# RS232.net
KiCad netlist of a schematic drawn in Altium Designer
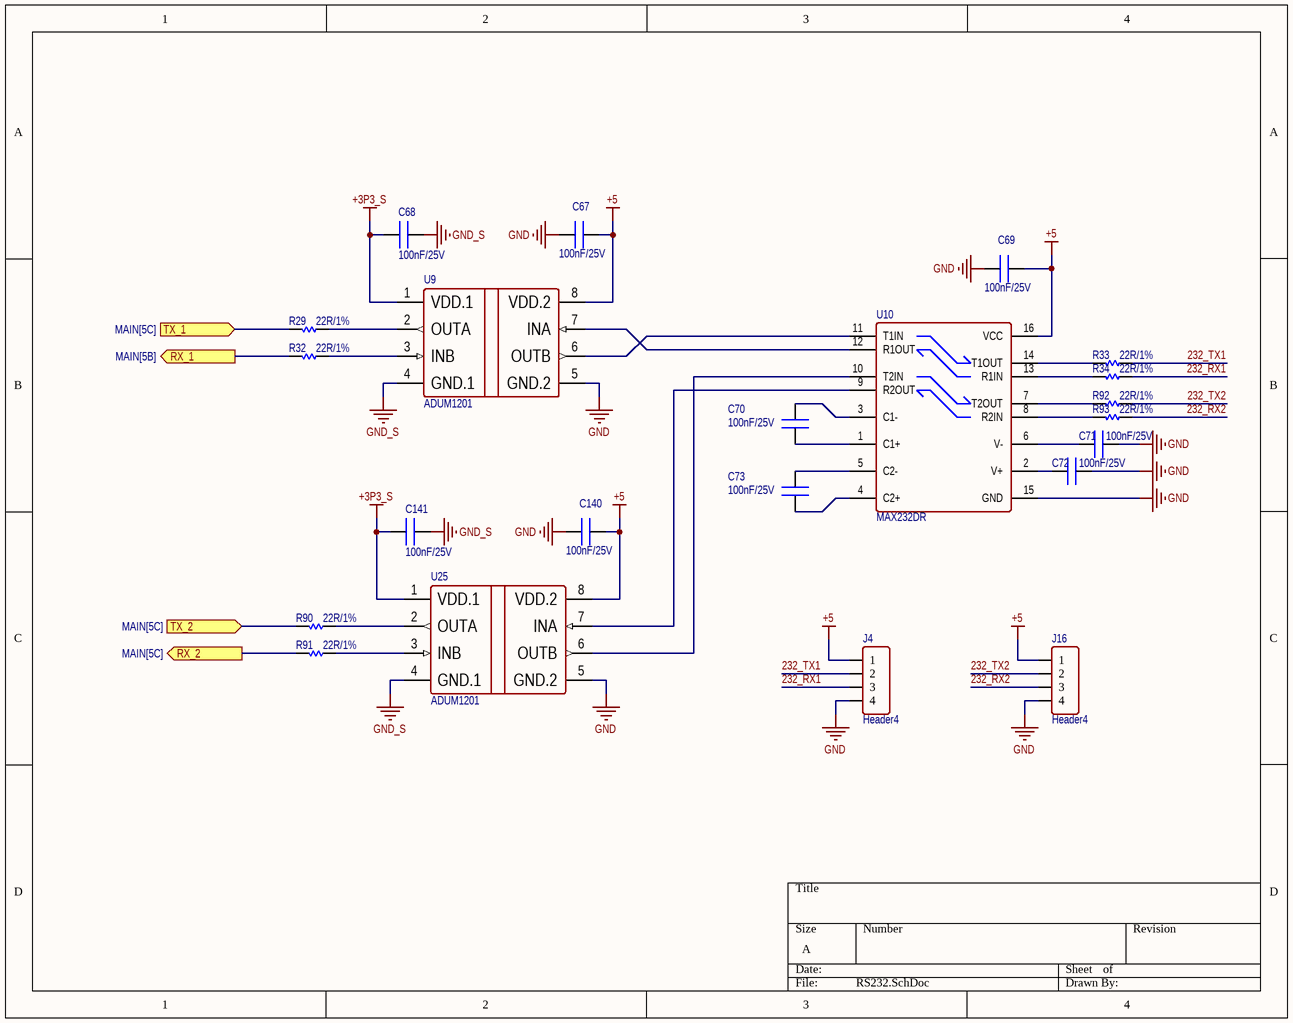
[diagram p0: RS232.SchDoc]

(export (version "E")
  (design (tool "Eeschema 10.0.6"))
  (components
    (comp (ref "C67")
      (value "100nF/25V")
      (footprint "CN-SMD-0603")
      (description "CL10B104KA8NNNC")
      (libsource (lib "Library") (part "CN"))
    )
    (comp (ref "C68")
      (value "100nF/25V")
      (footprint "CN-SMD-0603")
      (description "CL10B104KA8NNNC")
      (libsource (lib "Library") (part "CN"))
    )
    (comp (ref "C69")
      (value "100nF/25V")
      (footprint "CN-SMD-0603")
      (description "CL10B104KA8NNNC")
      (libsource (lib "Library") (part "CN"))
    )
    (comp (ref "C70")
      (value "100nF/25V")
      (footprint "CN-SMD-0603")
      (description "CL10B104KA8NNNC")
      (libsource (lib "Library") (part "CN"))
    )
    (comp (ref "C71")
      (value "100nF/25V")
      (footprint "CN-SMD-0603")
      (description "CL10B104KA8NNNC")
      (libsource (lib "Library") (part "CN"))
    )
    (comp (ref "C72")
      (value "100nF/25V")
      (footprint "CN-SMD-0603")
      (description "CL10B104KA8NNNC")
      (libsource (lib "Library") (part "CN"))
    )
    (comp (ref "C73")
      (value "100nF/25V")
      (footprint "CN-SMD-0603")
      (description "CL10B104KA8NNNC")
      (libsource (lib "Library") (part "CN"))
    )
    (comp (ref "C140")
      (value "100nF/25V")
      (footprint "CN-SMD-0603")
      (description "CL10B104KA8NNNC")
      (libsource (lib "Library") (part "CN"))
    )
    (comp (ref "C141")
      (value "100nF/25V")
      (footprint "CN-SMD-0603")
      (description "CL10B104KA8NNNC")
      (libsource (lib "Library") (part "CN"))
    )
    (comp (ref "J4")
      (value "Header4")
      (footprint "XH2.54-4-DIP")
      (description "Connector 4")
      (fields
        (field (name "MANUFACTURER") "Würth Elektronik eiSos GmbH")
        (field (name "PARTNO") "613002143121")
        (field (name "CREATED BY") "Karrer Zheng")
      )
      (libsource (lib "Library") (part "Header4"))
    )
    (comp (ref "J16")
      (value "Header4")
      (footprint "XH2.54-4-DIP")
      (description "Connector 4")
      (fields
        (field (name "MANUFACTURER") "Würth Elektronik eiSos GmbH")
        (field (name "PARTNO") "613002143121")
        (field (name "CREATED BY") "Karrer Zheng")
      )
      (libsource (lib "Library") (part "Header4"))
    )
    (comp (ref "R29")
      (value "22R/1%")
      (footprint "RES-SMD-0603")
      (description "ERJ-3EKF22R0V")
      (libsource (lib "Library") (part "Res-SMD"))
    )
    (comp (ref "R32")
      (value "22R/1%")
      (footprint "RES-SMD-0603")
      (description "ERJ-3EKF22R0V")
      (libsource (lib "Library") (part "Res-SMD"))
    )
    (comp (ref "R33")
      (value "22R/1%")
      (footprint "RES-SMD-0603")
      (description "ERJ-3EKF22R0V")
      (libsource (lib "Library") (part "Res-SMD"))
    )
    (comp (ref "R34")
      (value "22R/1%")
      (footprint "RES-SMD-0603")
      (description "ERJ-3EKF22R0V")
      (libsource (lib "Library") (part "Res-SMD"))
    )
    (comp (ref "R90")
      (value "22R/1%")
      (footprint "RES-SMD-0603")
      (description "ERJ-3EKF22R0V")
      (libsource (lib "Library") (part "Res-SMD"))
    )
    (comp (ref "R91")
      (value "22R/1%")
      (footprint "RES-SMD-0603")
      (description "ERJ-3EKF22R0V")
      (libsource (lib "Library") (part "Res-SMD"))
    )
    (comp (ref "R92")
      (value "22R/1%")
      (footprint "RES-SMD-0603")
      (description "ERJ-3EKF22R0V")
      (libsource (lib "Library") (part "Res-SMD"))
    )
    (comp (ref "R93")
      (value "22R/1%")
      (footprint "RES-SMD-0603")
      (description "ERJ-3EKF22R0V")
      (libsource (lib "Library") (part "Res-SMD"))
    )
    (comp (ref "U9")
      (value "ADUM1201")
      (footprint "SO8")
      (description "Dual-Channel Digital Isolators")
      (libsource (lib "Library") (part "ADUM1201"))
    )
    (comp (ref "U10") (value "MAX232DR") (footprint "SO16") (libsource (lib "Library") (part "MAX3232")))
    (comp (ref "U25")
      (value "ADUM1201")
      (footprint "SO8")
      (description "Dual-Channel Digital Isolators")
      (libsource (lib "Library") (part "ADUM1201"))
    )
  )
  (nets
    (net (code "1") (name "+3P3_S") (class "Default")
      (node (ref "C141") (pin "2") (pinfunction "2_2") (pintype "passive"))
      (node (ref "C68") (pin "2") (pinfunction "2_2") (pintype "passive"))
      (node (ref "U25") (pin "1") (pinfunction "VDD.1_1") (pintype "passive"))
      (node (ref "U9") (pin "1") (pinfunction "VDD.1_1") (pintype "passive"))
    )
    (net (code "2") (name "+5") (class "Default")
      (node (ref "C140") (pin "1") (pinfunction "1_1") (pintype "passive"))
      (node (ref "C67") (pin "1") (pinfunction "1_1") (pintype "passive"))
      (node (ref "C69") (pin "1") (pinfunction "1_1") (pintype "passive"))
      (node (ref "J16") (pin "1") (pinfunction "1_1") (pintype "passive"))
      (node (ref "J4") (pin "1") (pinfunction "1_1") (pintype "passive"))
      (node (ref "U10") (pin "16") (pinfunction "VCC_16") (pintype "power_in"))
      (node (ref "U25") (pin "8") (pinfunction "VDD.2_8") (pintype "passive"))
      (node (ref "U9") (pin "8") (pinfunction "VDD.2_8") (pintype "passive"))
    )
    (net (code "3") (name "/232_RX1") (class "Default")
      (node (ref "J4") (pin "3") (pinfunction "3_3") (pintype "passive"))
      (node (ref "R34") (pin "1") (pinfunction "1_1") (pintype "passive"))
    )
    (net (code "4") (name "/232_RX2") (class "Default")
      (node (ref "J16") (pin "3") (pinfunction "3_3") (pintype "passive"))
      (node (ref "R93") (pin "1") (pinfunction "1_1") (pintype "passive"))
    )
    (net (code "5") (name "/232_TX1") (class "Default")
      (node (ref "J4") (pin "2") (pinfunction "2_2") (pintype "passive"))
      (node (ref "R33") (pin "1") (pinfunction "1_1") (pintype "passive"))
    )
    (net (code "6") (name "/232_TX2") (class "Default")
      (node (ref "J16") (pin "2") (pinfunction "2_2") (pintype "passive"))
      (node (ref "R92") (pin "1") (pinfunction "1_1") (pintype "passive"))
    )
    (net (code "7") (name "/RX_1") (class "Default")
      (node (ref "R32") (pin "2") (pinfunction "2_2") (pintype "passive"))
    )
    (net (code "8") (name "/RX_2") (class "Default")
      (node (ref "R91") (pin "2") (pinfunction "2_2") (pintype "passive"))
    )
    (net (code "9") (name "/TX_1") (class "Default")
      (node (ref "R29") (pin "2") (pinfunction "2_2") (pintype "passive"))
    )
    (net (code "10") (name "/TX_2") (class "Default")
      (node (ref "R90") (pin "2") (pinfunction "2_2") (pintype "passive"))
    )
    (net (code "11") (name "GND") (class "Default")
      (node (ref "C140") (pin "2") (pinfunction "2_2") (pintype "passive"))
      (node (ref "C67") (pin "2") (pinfunction "2_2") (pintype "passive"))
      (node (ref "C69") (pin "2") (pinfunction "2_2") (pintype "passive"))
      (node (ref "C71") (pin "1") (pinfunction "1_1") (pintype "passive"))
      (node (ref "C72") (pin "1") (pinfunction "1_1") (pintype "passive"))
      (node (ref "J16") (pin "4") (pinfunction "4_4") (pintype "passive"))
      (node (ref "J4") (pin "4") (pinfunction "4_4") (pintype "passive"))
      (node (ref "U10") (pin "15") (pinfunction "GND_15") (pintype "power_in"))
      (node (ref "U25") (pin "5") (pinfunction "GND.2_5") (pintype "passive"))
      (node (ref "U9") (pin "5") (pinfunction "GND.2_5") (pintype "passive"))
    )
    (net (code "12") (name "GND_S") (class "Default")
      (node (ref "C141") (pin "1") (pinfunction "1_1") (pintype "passive"))
      (node (ref "C68") (pin "1") (pinfunction "1_1") (pintype "passive"))
      (node (ref "U25") (pin "4") (pinfunction "GND.1_4") (pintype "passive"))
      (node (ref "U9") (pin "4") (pinfunction "GND.1_4") (pintype "passive"))
    )
    (net (code "13") (name "Net-(U9-INB)") (class "Default")
      (node (ref "R32") (pin "1") (pinfunction "1_1") (pintype "passive"))
      (node (ref "U9") (pin "3") (pinfunction "INB_3") (pintype "input"))
    )
    (net (code "14") (name "Net-(U9-OUTA)") (class "Default")
      (node (ref "R29") (pin "1") (pinfunction "1_1") (pintype "passive"))
      (node (ref "U9") (pin "2") (pinfunction "OUTA_2") (pintype "output"))
    )
    (net (code "15") (name "Net-(U10-C1+)") (class "Default")
      (node (ref "C70") (pin "1") (pinfunction "1_1") (pintype "passive"))
      (node (ref "U10") (pin "1") (pinfunction "C1+_1") (pintype "power_in"))
    )
    (net (code "16") (name "Net-(U10-C1-)") (class "Default")
      (node (ref "C70") (pin "2") (pinfunction "2_2") (pintype "passive"))
      (node (ref "U10") (pin "3") (pinfunction "C1-_3") (pintype "passive"))
    )
    (net (code "17") (name "Net-(U10-C2+)") (class "Default")
      (node (ref "C73") (pin "1") (pinfunction "1_1") (pintype "passive"))
      (node (ref "U10") (pin "4") (pinfunction "C2+_4") (pintype "passive"))
    )
    (net (code "18") (name "Net-(U10-C2-)") (class "Default")
      (node (ref "C73") (pin "2") (pinfunction "2_2") (pintype "passive"))
      (node (ref "U10") (pin "5") (pinfunction "C2-_5") (pintype "power_in"))
    )
    (net (code "19") (name "Net-(U10-R1IN)") (class "Default")
      (node (ref "R34") (pin "2") (pinfunction "2_2") (pintype "passive"))
      (node (ref "U10") (pin "13") (pinfunction "R1IN_13") (pintype "passive"))
    )
    (net (code "20") (name "Net-(U10-R1OUT)") (class "Default")
      (node (ref "U10") (pin "12") (pinfunction "R1OUT_12") (pintype "passive"))
      (node (ref "U9") (pin "7") (pinfunction "INA_7") (pintype "input"))
    )
    (net (code "21") (name "Net-(U10-R2IN)") (class "Default")
      (node (ref "R93") (pin "2") (pinfunction "2_2") (pintype "passive"))
      (node (ref "U10") (pin "8") (pinfunction "R2IN_8") (pintype "passive"))
    )
    (net (code "22") (name "Net-(U10-R2OUT)") (class "Default")
      (node (ref "U10") (pin "9") (pinfunction "R2OUT_9") (pintype "passive"))
      (node (ref "U25") (pin "7") (pinfunction "INA_7") (pintype "input"))
    )
    (net (code "23") (name "Net-(U10-T1IN)") (class "Default")
      (node (ref "U10") (pin "11") (pinfunction "T1IN_11") (pintype "passive"))
      (node (ref "U9") (pin "6") (pinfunction "OUTB_6") (pintype "output"))
    )
    (net (code "24") (name "Net-(U10-T1OUT)") (class "Default")
      (node (ref "R33") (pin "2") (pinfunction "2_2") (pintype "passive"))
      (node (ref "U10") (pin "14") (pinfunction "T1OUT_14") (pintype "power_in"))
    )
    (net (code "25") (name "Net-(U10-T2IN)") (class "Default")
      (node (ref "U10") (pin "10") (pinfunction "T2IN_10") (pintype "passive"))
      (node (ref "U25") (pin "6") (pinfunction "OUTB_6") (pintype "output"))
    )
    (net (code "26") (name "Net-(U10-T2OUT)") (class "Default")
      (node (ref "R92") (pin "2") (pinfunction "2_2") (pintype "passive"))
      (node (ref "U10") (pin "7") (pinfunction "T2OUT_7") (pintype "passive"))
    )
    (net (code "27") (name "Net-(U10-V+)") (class "Default")
      (node (ref "C72") (pin "2") (pinfunction "2_2") (pintype "passive"))
      (node (ref "U10") (pin "2") (pinfunction "V+_2") (pintype "passive"))
    )
    (net (code "28") (name "Net-(U10-V-)") (class "Default")
      (node (ref "C71") (pin "2") (pinfunction "2_2") (pintype "passive"))
      (node (ref "U10") (pin "6") (pinfunction "V-_6") (pintype "passive"))
    )
    (net (code "29") (name "Net-(U25-INB)") (class "Default")
      (node (ref "R91") (pin "1") (pinfunction "1_1") (pintype "passive"))
      (node (ref "U25") (pin "3") (pinfunction "INB_3") (pintype "input"))
    )
    (net (code "30") (name "Net-(U25-OUTA)") (class "Default")
      (node (ref "R90") (pin "1") (pinfunction "1_1") (pintype "passive"))
      (node (ref "U25") (pin "2") (pinfunction "OUTA_2") (pintype "output"))
    )
  )
)
